# Sheet1.net
KiCad netlist of a schematic drawn in Altium Designer
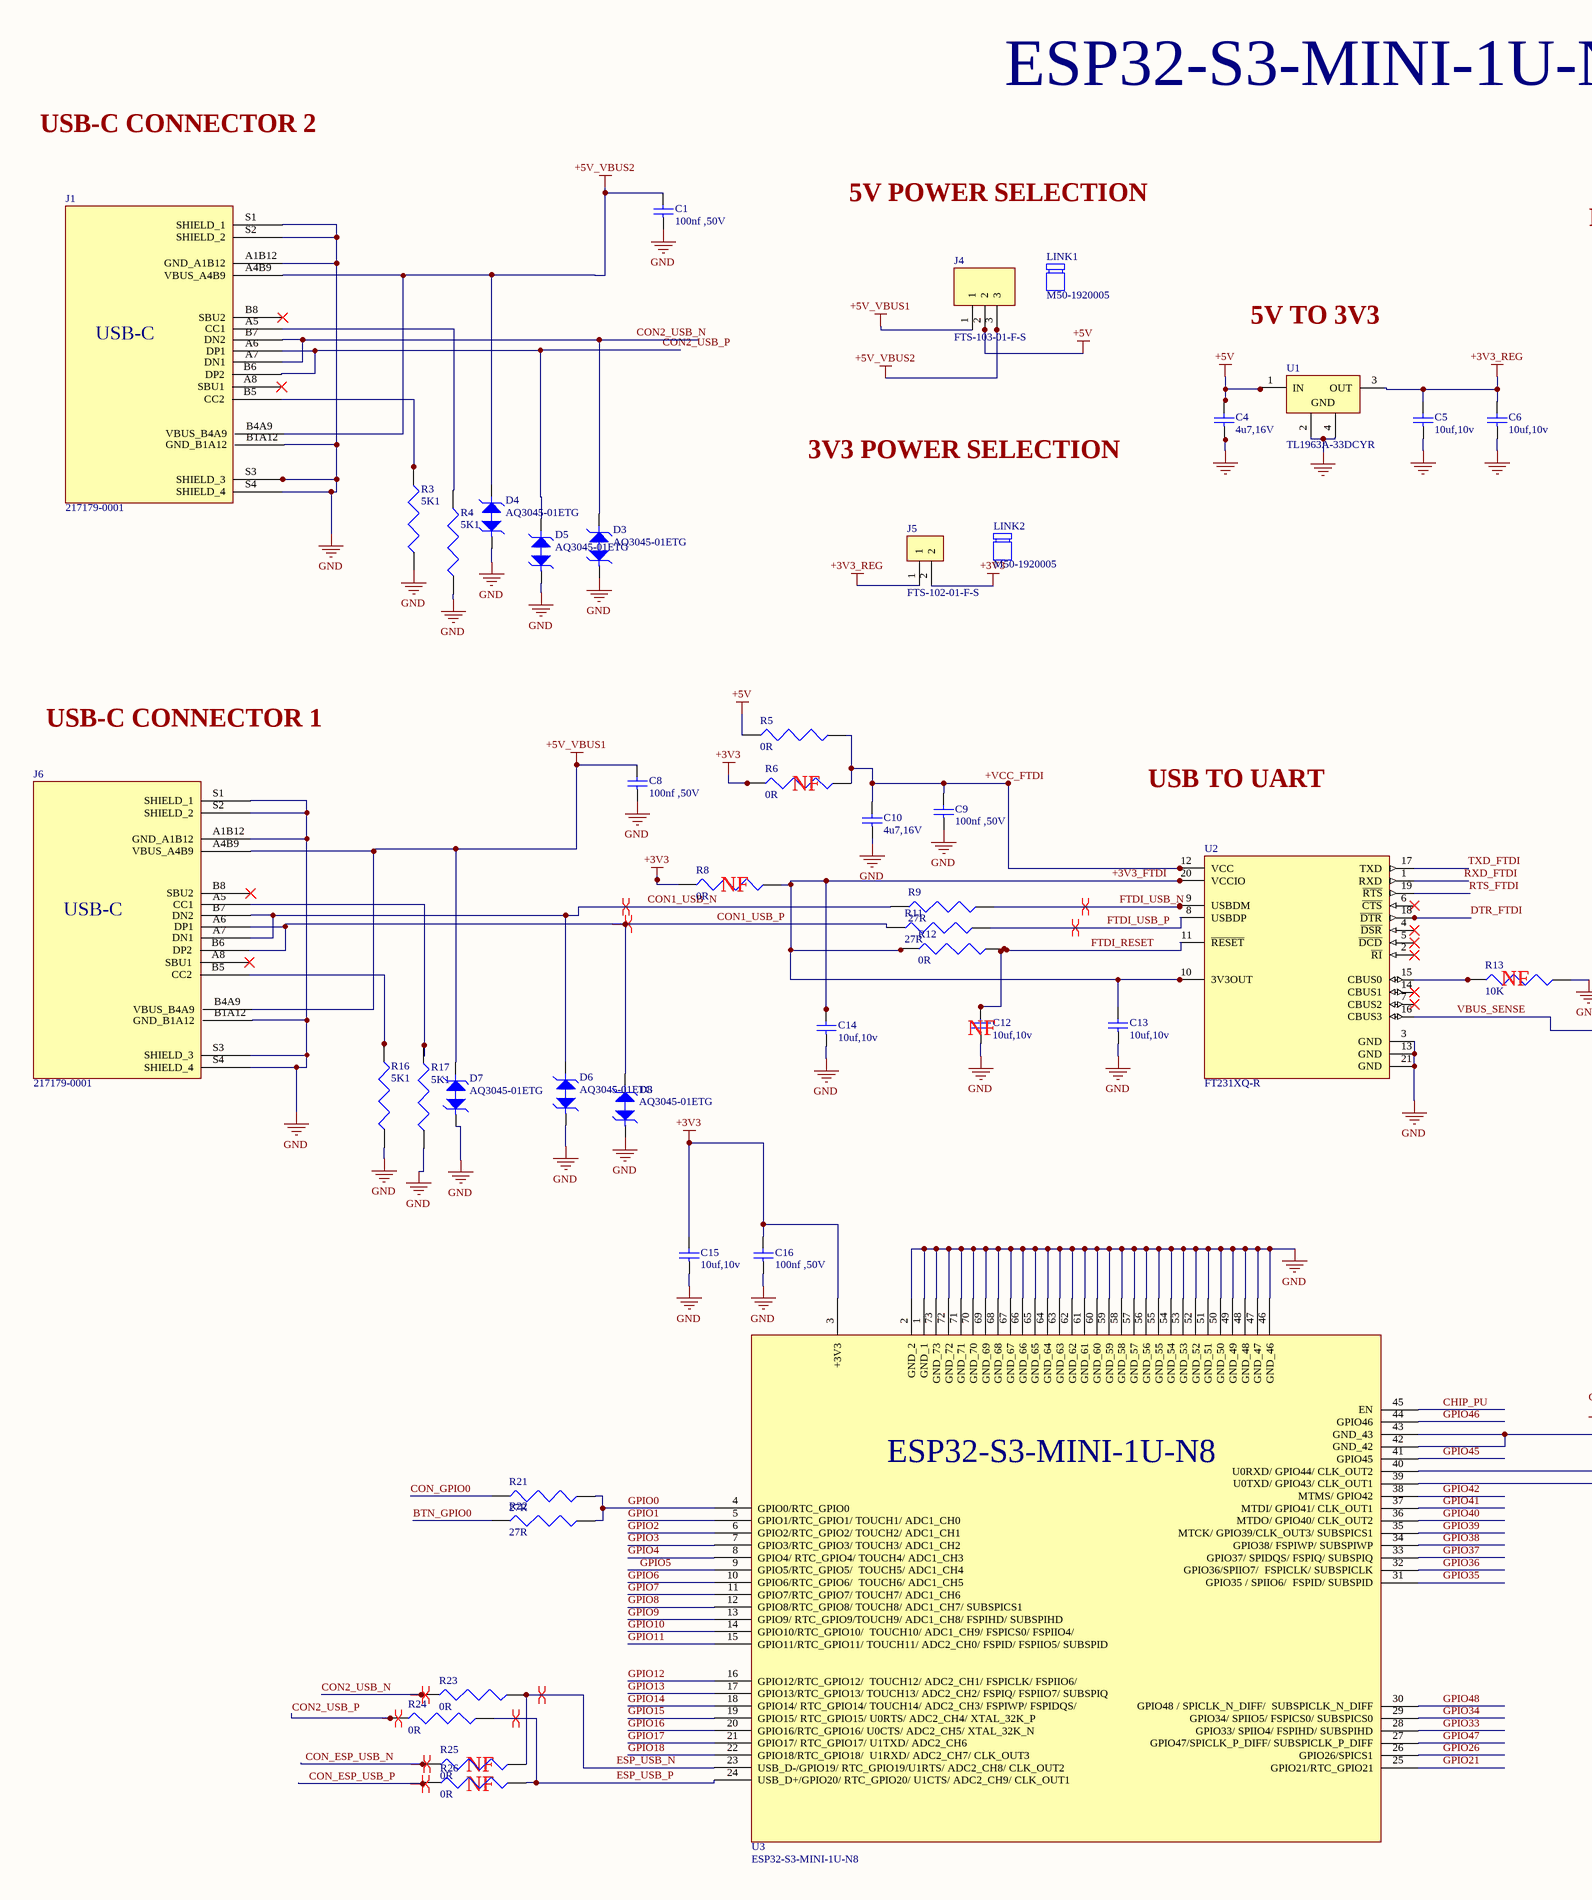
[diagram p0: Sheet1.SchDoc, left]
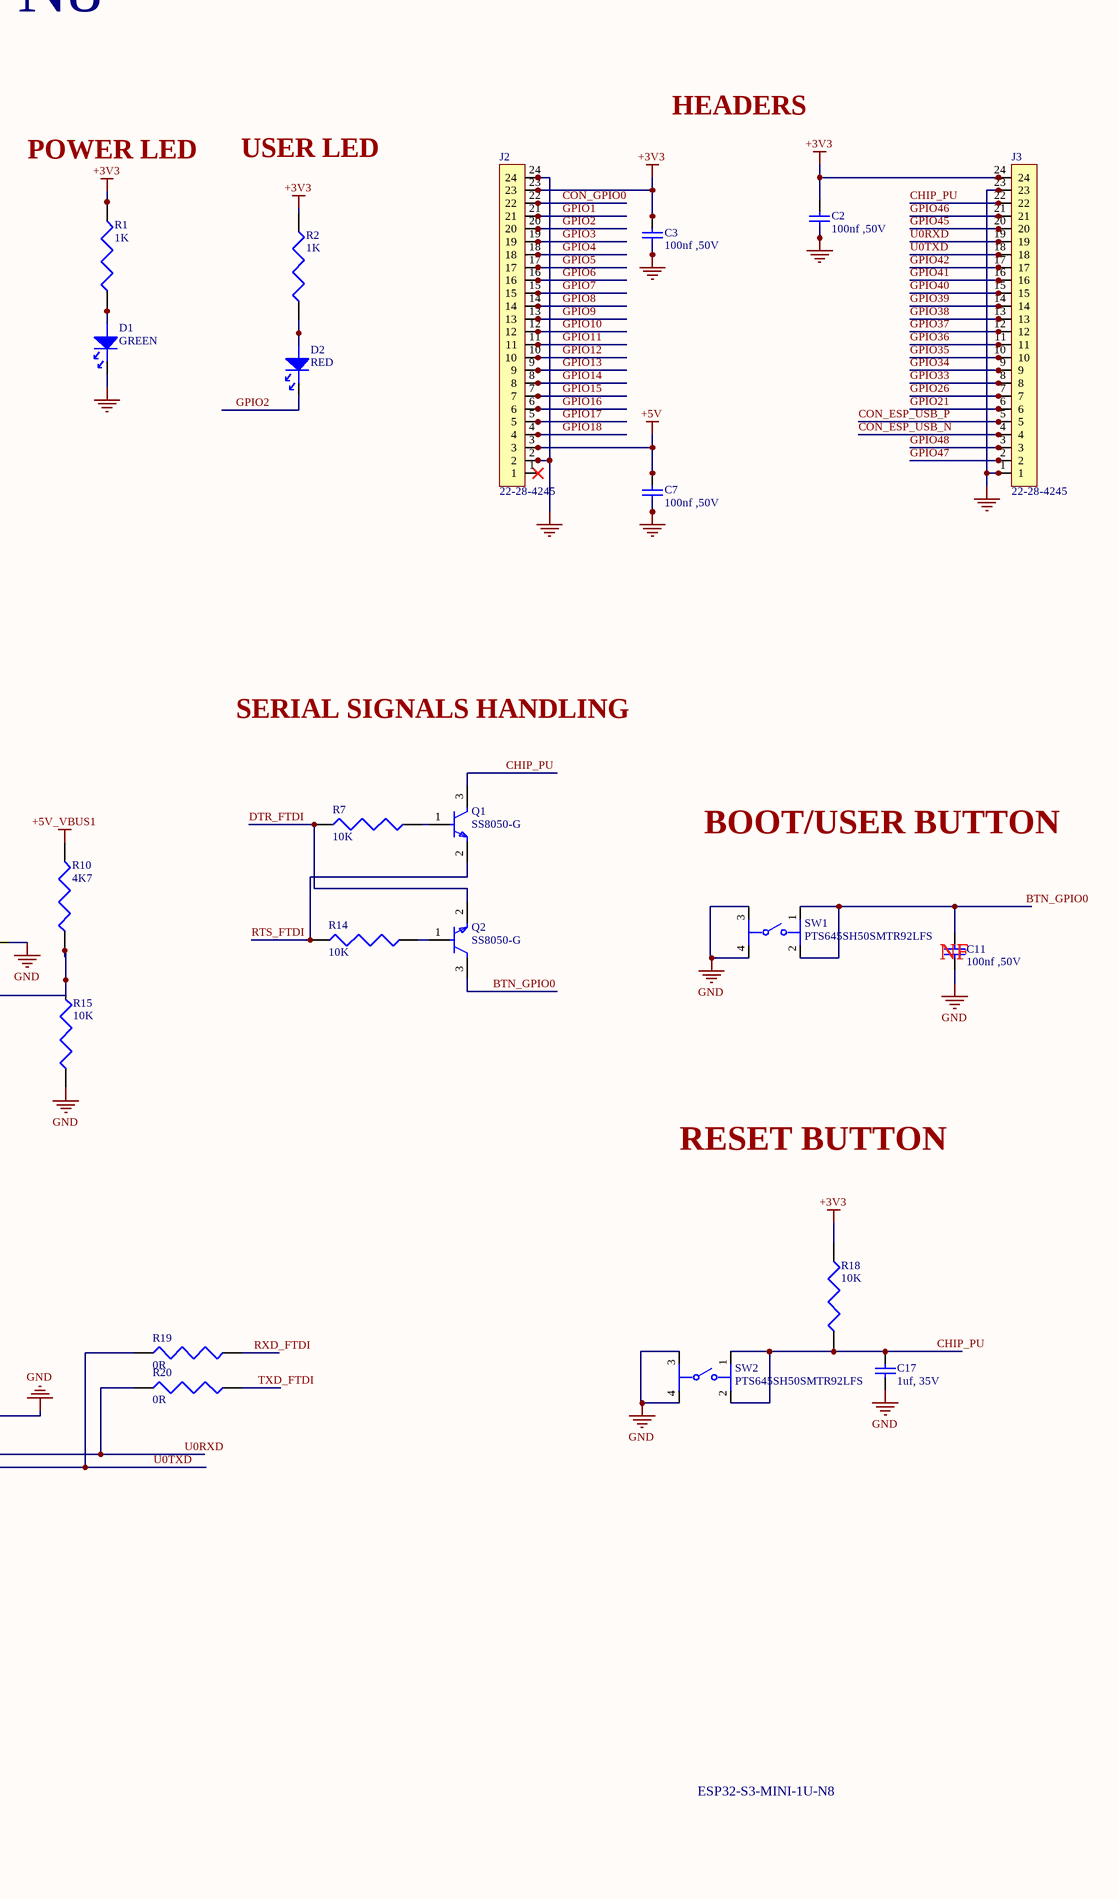
[diagram p1: Sheet1.SchDoc, right]

(export (version "E")
  (design (tool "Eeschema 10.0.6"))
  (components
    (comp (ref "C1")
      (value "100nf ,50V")
      (footprint "CAPC1005X70N")
      (description "CAP CER 0.1UF 10V X7R 0402")
      (fields
        (field (name "MANUFACTURER") "Samsung")
        (field (name "MANUFACTURER PART NUMBER") "CL05B104KP5NNNC")
      )
      (libsource (lib "Schlib1") (part "CL05B104KP5NNNC"))
    )
    (comp (ref "C2")
      (value "100nf ,50V")
      (footprint "CAPC1005X70N")
      (description "CAP CER 0.1UF 10V X7R 0402")
      (fields
        (field (name "MANUFACTURER") "Samsung")
        (field (name "MANUFACTURER PART NUMBER") "CL05B104KP5NNNC")
      )
      (libsource (lib "Schlib1") (part "CL05B104KP5NNNC"))
    )
    (comp (ref "C3")
      (value "100nf ,50V")
      (footprint "CAPC1005X70N")
      (description "CAP CER 0.1UF 10V X7R 0402")
      (fields
        (field (name "MANUFACTURER") "Samsung")
        (field (name "MANUFACTURER PART NUMBER") "CL05B104KP5NNNC")
      )
      (libsource (lib "Schlib1") (part "CL05B104KP5NNNC"))
    )
    (comp (ref "C4")
      (value "4u7,16V")
      (footprint "CAPC1005X70N")
      (description "CAP CER 4.7UF 16V X5R 0402")
      (fields
        (field (name "MANUFACTURER") "Samsung")
        (field (name "MANUFACTURER PART NUMBER") "CL05A475MO5NUNC")
      )
      (libsource (lib "Schlib1") (part "CL05A475MO5NUNC"))
    )
    (comp (ref "C5")
      (value "10uf,10v")
      (footprint "CAPC1005X70N")
      (description "CAP CER 10UF 10V X5R 0402")
      (fields
        (field (name "MANUFACTURER") "Samsung")
        (field (name "MANUFACTURER PART NUMBER") "CL05A106MP8NUB8")
      )
      (libsource (lib "Schlib1") (part "CL05A106MP8NUB8"))
    )
    (comp (ref "C6")
      (value "10uf,10v")
      (footprint "CAPC1005X70N")
      (description "CAP CER 10UF 10V X5R 0402")
      (fields
        (field (name "MANUFACTURER") "Samsung")
        (field (name "MANUFACTURER PART NUMBER") "CL05A106MP8NUB8")
      )
      (libsource (lib "Schlib1") (part "CL05A106MP8NUB8"))
    )
    (comp (ref "C7")
      (value "100nf ,50V")
      (footprint "CAPC1005X70N")
      (description "CAP CER 0.1UF 10V X7R 0402")
      (fields
        (field (name "MANUFACTURER") "Samsung")
        (field (name "MANUFACTURER PART NUMBER") "CL05B104KP5NNNC")
      )
      (libsource (lib "Schlib1") (part "CL05B104KP5NNNC"))
    )
    (comp (ref "C8")
      (value "100nf ,50V")
      (footprint "CAPC1005X70N")
      (description "CAP CER 0.1UF 10V X7R 0402")
      (fields
        (field (name "MANUFACTURER") "Samsung")
        (field (name "MANUFACTURER PART NUMBER") "CL05B104KP5NNNC")
      )
      (libsource (lib "Schlib1") (part "CL05B104KP5NNNC"))
    )
    (comp (ref "C9")
      (value "100nf ,50V")
      (footprint "CAPC1005X70N")
      (description "CAP CER 0.1UF 10V X7R 0402")
      (fields
        (field (name "MANUFACTURER") "Samsung")
        (field (name "MANUFACTURER PART NUMBER") "CL05B104KP5NNNC")
      )
      (libsource (lib "Schlib1") (part "CL05B104KP5NNNC"))
    )
    (comp (ref "C10")
      (value "4u7,16V")
      (footprint "CAPC1005X70N")
      (description "CAP CER 4.7UF 16V X5R 0402")
      (fields
        (field (name "MANUFACTURER") "Samsung")
        (field (name "MANUFACTURER PART NUMBER") "CL05A475MO5NUNC")
      )
      (libsource (lib "Schlib1") (part "CL05A475MO5NUNC"))
    )
    (comp (ref "C11")
      (value "100nf ,50V")
      (footprint "CAPC1005X70N")
      (description "CAP CER 0.1UF 10V X7R 0402")
      (fields
        (field (name "MANUFACTURER") "Samsung")
        (field (name "MANUFACTURER PART NUMBER") "CL05B104KP5NNNC")
      )
      (libsource (lib "Schlib1") (part "CL05B104KP5NNNC"))
    )
    (comp (ref "C12")
      (value "10uf,10v")
      (footprint "CAPC1005X70N")
      (description "CAP CER 10UF 10V X5R 0402")
      (fields
        (field (name "MANUFACTURER") "Samsung")
        (field (name "MANUFACTURER PART NUMBER") "CL05A106MP8NUB8")
      )
      (libsource (lib "Schlib1") (part "CL05A106MP8NUB8"))
    )
    (comp (ref "C13")
      (value "10uf,10v")
      (footprint "CAPC1005X70N")
      (description "CAP CER 10UF 10V X5R 0402")
      (fields
        (field (name "MANUFACTURER") "Samsung")
        (field (name "MANUFACTURER PART NUMBER") "CL05A106MP8NUB8")
      )
      (libsource (lib "Schlib1") (part "CL05A106MP8NUB8"))
    )
    (comp (ref "C14")
      (value "10uf,10v")
      (footprint "CAPC1005X70N")
      (description "CAP CER 10UF 10V X5R 0402")
      (fields
        (field (name "MANUFACTURER") "Samsung")
        (field (name "MANUFACTURER PART NUMBER") "CL05A106MP8NUB8")
      )
      (libsource (lib "Schlib1") (part "CL05A106MP8NUB8"))
    )
    (comp (ref "C15")
      (value "10uf,10v")
      (footprint "CAPC1005X70N")
      (description "CAP CER 10UF 10V X5R 0402")
      (fields
        (field (name "MANUFACTURER") "Samsung")
        (field (name "MANUFACTURER PART NUMBER") "CL05A106MP8NUB8")
      )
      (libsource (lib "Schlib1") (part "CL05A106MP8NUB8"))
    )
    (comp (ref "C16")
      (value "100nf ,50V")
      (footprint "CAPC1005X70N")
      (description "CAP CER 0.1UF 10V X7R 0402")
      (fields
        (field (name "MANUFACTURER") "Samsung")
        (field (name "MANUFACTURER PART NUMBER") "CL05B104KP5NNNC")
      )
      (libsource (lib "Schlib1") (part "CL05B104KP5NNNC"))
    )
    (comp (ref "C17")
      (value "1uf, 35V")
      (footprint "CAPC1005X70N")
      (description "CAP CER 1UF 35V X5R 0402")
      (fields
        (field (name "MANUFACTURER") "Samsung")
        (field (name "MANUFACTURER PART NUMBER") "CL05A105KL5NRNC")
      )
      (libsource (lib "Schlib1") (part "CL05A105KL5NRNC"))
    )
    (comp (ref "D1")
      (value "GREEN")
      (footprint "LED0402G")
      (description "LED YLW-GRN 0402 SMD")
      (fields
        (field (name "MANUFACTURER") "Vishay")
        (field (name "MANUFACTURER PART NUMBER") "VLMG1500-GS08")
      )
      (libsource (lib "Schlib1") (part "VLMG1500-GS08"))
    )
    (comp (ref "D2")
      (value "RED")
      (footprint "LED0402G")
      (description "LED RED 0402 SMD")
      (fields
        (field (name "MANUFACTURER") "Vishay")
        (field (name "MANUFACTURER PART NUMBER") "VLMS1500-GS08")
      )
      (libsource (lib "Schlib1") (part "VLMS1500-GS08"))
    )
    (comp (ref "D3")
      (value "AQ3045-01ETG")
      (footprint "SOD882")
      (description "TVS DIODE 5.3VWM 12VC SOD882")
      (fields (field (name "MANUFACTURER") "Littelfuse"))
      (libsource (lib "Schlib1") (part "AQ3045-01ETG"))
    )
    (comp (ref "D4")
      (value "AQ3045-01ETG")
      (footprint "SOD882")
      (description "TVS DIODE 5.3VWM 12VC SOD882")
      (fields (field (name "MANUFACTURER") "Littelfuse"))
      (libsource (lib "Schlib1") (part "AQ3045-01ETG"))
    )
    (comp (ref "D5")
      (value "AQ3045-01ETG")
      (footprint "SOD882")
      (description "TVS DIODE 5.3VWM 12VC SOD882")
      (fields (field (name "MANUFACTURER") "Littelfuse"))
      (libsource (lib "Schlib1") (part "AQ3045-01ETG"))
    )
    (comp (ref "D6")
      (value "AQ3045-01ETG")
      (footprint "SOD882")
      (description "TVS DIODE 5.3VWM 12VC SOD882")
      (fields (field (name "MANUFACTURER") "Littelfuse"))
      (libsource (lib "Schlib1") (part "AQ3045-01ETG"))
    )
    (comp (ref "D7")
      (value "AQ3045-01ETG")
      (footprint "SOD882")
      (description "TVS DIODE 5.3VWM 12VC SOD882")
      (fields (field (name "MANUFACTURER") "Littelfuse"))
      (libsource (lib "Schlib1") (part "AQ3045-01ETG"))
    )
    (comp (ref "D8")
      (value "AQ3045-01ETG")
      (footprint "SOD882")
      (description "TVS DIODE 5.3VWM 12VC SOD882")
      (fields (field (name "MANUFACTURER") "Littelfuse"))
      (libsource (lib "Schlib1") (part "AQ3045-01ETG"))
    )
    (comp (ref "J1")
      (value "217179-0001")
      (footprint "FP-2171790001-MFG")
      (description "CONN RCP USB2.0 TYP C 24P SMD RA")
      (fields (field (name "MANUFACTURER") "Molex"))
      (libsource (lib "Schlib1") (part "217179-0001"))
    )
    (comp (ref "J2")
      (value "22-28-4245")
      (footprint "HDR_1X24_2.54mm")
      (description "CONN HEADER VERT 24POS 2.54MM")
      (fields (field (name "MANUFACTURER") "Molex") (field (name "LCSC PART NUMBER") "C7145888"))
      (libsource (lib "") (part "22-28-4245_1"))
    )
    (comp (ref "J3")
      (value "22-28-4245")
      (footprint "HDR_1X24_2.54mm")
      (description "CONN HEADER VERT 24POS 2.54MM")
      (fields (field (name "MANUFACTURER") "Molex") (field (name "LCSC PART NUMBER") "C7145888"))
      (libsource (lib "Schlib1") (part "22-28-4245"))
    )
    (comp (ref "J4")
      (value "FTS-103-01-F-S")
      (footprint "HDR_1X3_2.54mm - duplicate")
      (description "CONN HEADER VERT 3POS 1.27MM")
      (fields (field (name "MANUFACTURER") "Samtec") (field (name "LCSC PART NUMBER") "C3333578"))
      (libsource (lib "Schlib1") (part "FTS-103-01-F-S"))
    )
    (comp (ref "J5")
      (value "FTS-102-01-F-S")
      (footprint "HDR_1X2_2.54mm")
      (description "CONN HEADER VERT 2POS 1.27MM")
      (fields (field (name "MANUFACTURER") "Samtec") (field (name "LCSC PART NUMBER") "C6045317"))
      (libsource (lib "Schlib1") (part "FTS-102-01-F-S"))
    )
    (comp (ref "J6")
      (value "217179-0001")
      (footprint "FP-2171790001-MFG")
      (description "CONN RCP USB2.0 TYP C 24P SMD RA")
      (fields (field (name "MANUFACTURER") "Molex"))
      (libsource (lib "Schlib1") (part "217179-0001"))
    )
    (comp (ref "LINK1")
      (value "M50-1920005")
      (description "CONN SHUNT 1.27MM RED")
      (fields (field (name "MANUFACTURER") "Harwin") (field (name "LCSC PART NUMBER") "C6985646"))
      (libsource (lib "Schlib1") (part "M50-1920005"))
    )
    (comp (ref "LINK2")
      (value "M50-1920005")
      (description "CONN SHUNT 1.27MM RED")
      (fields (field (name "MANUFACTURER") "Harwin") (field (name "LCSC PART NUMBER") "C6985646"))
      (libsource (lib "Schlib1") (part "M50-1920005"))
    )
    (comp (ref "Q1")
      (value "SS8050-G")
      (footprint "FP-SS8050-G-IPC_B")
      (description "TRANS NPN 25V 1.5A SOT23-3")
      (fields (field (name "MANUFACTURER") "Comchip") (field (name "PARAMETER 1LCSC PART NUMBER") "C164886"))
      (libsource (lib "Schlib1") (part "SS8050-G"))
    )
    (comp (ref "Q2")
      (value "SS8050-G")
      (footprint "FP-SS8050-G-IPC_B")
      (description "TRANS NPN 25V 1.5A SOT23-3")
      (fields (field (name "MANUFACTURER") "Comchip") (field (name "PARAMETER 1LCSC PART NUMBER") "C164886"))
      (libsource (lib "Schlib1") (part "SS8050-G"))
    )
    (comp (ref "R1")
      (value "1K")
      (footprint "RESC1005X37N")
      (description "RES 1K OHM 1% 1/16W 0402")
      (fields
        (field (name "MANUFACTURER") "Yageo")
        (field (name "MANUFACTURER PART NUMBER") "RC0402FR-071KL")
      )
      (libsource (lib "Schlib1") (part "RC0402FR-071KL"))
    )
    (comp (ref "R2")
      (value "1K")
      (footprint "RESC1005X37N")
      (description "RES 1K OHM 1% 1/16W 0402")
      (fields
        (field (name "MANUFACTURER") "Yageo")
        (field (name "MANUFACTURER PART NUMBER") "RC0402FR-071KL")
      )
      (libsource (lib "Schlib1") (part "RC0402FR-071KL"))
    )
    (comp (ref "R3")
      (value "5K1")
      (footprint "RESC1005X37N")
      (description "RES SMD 5.1K OHM 1% 1/16W 0402")
      (fields
        (field (name "MANUFACTURER") "Yageo")
        (field (name "MANUFACTURER PART NUMBER") "AC0402FR-075K1L")
      )
      (libsource (lib "Schlib1") (part "AC0402FR-075K1L"))
    )
    (comp (ref "R4")
      (value "5K1")
      (footprint "RESC1005X37N")
      (description "RES SMD 5.1K OHM 1% 1/16W 0402")
      (fields
        (field (name "MANUFACTURER") "Yageo")
        (field (name "MANUFACTURER PART NUMBER") "AC0402FR-075K1L")
      )
      (libsource (lib "Schlib1") (part "AC0402FR-075K1L"))
    )
    (comp (ref "R5")
      (value "0R")
      (footprint "RESC1005X37N")
      (description "RES 0 OHM JUMPER 1/16W 0402")
      (fields
        (field (name "MANUFACTURER") "Yageo")
        (field (name "MANUFACTURER PART NUMBER") "RC0402JR-070RL")
      )
      (libsource (lib "Schlib1") (part "RC0402JR-070RL (2)"))
    )
    (comp (ref "R6")
      (value "0R")
      (footprint "RESC1005X37N")
      (description "RES 0 OHM JUMPER 1/16W 0402")
      (fields
        (field (name "MANUFACTURER") "Yageo")
        (field (name "MANUFACTURER PART NUMBER") "RC0402JR-070RL")
      )
      (libsource (lib "Schlib1") (part "RC0402JR-070RL (2)"))
    )
    (comp (ref "R7")
      (value "10K")
      (footprint "RESC1005X37N")
      (description "RES SMD 10K OHM 1% 1/16W 0402")
      (fields
        (field (name "MANUFACTURER") "Yageo")
        (field (name "MANUFACTURER PART NUMBER") "AC0402FR-0710KL")
      )
      (libsource (lib "Schlib1") (part "AC0402FR-0710KL"))
    )
    (comp (ref "R8")
      (value "0R")
      (footprint "RESC1005X37N")
      (description "RES 0 OHM JUMPER 1/16W 0402")
      (fields
        (field (name "MANUFACTURER") "Yageo")
        (field (name "MANUFACTURER PART NUMBER") "RC0402JR-070RL")
      )
      (libsource (lib "Schlib1") (part "RC0402JR-070RL (2)"))
    )
    (comp (ref "R9")
      (value "27R")
      (footprint "RESC1005X37N")
      (description "RES 27R OHM JUMPER 1/16W 0402")
      (fields
        (field (name "MANUFACTURER") "Yageo")
        (field (name "MANUFACTURER PART NUMBER") "RC0402FR-0727RL")
      )
      (libsource (lib "Schlib1") (part "RC0402FR-0727RL"))
    )
    (comp (ref "R10")
      (value "4K7")
      (footprint "RESC1005X37N")
      (description "RES 4.7K OHM 1% 1/16W 0402")
      (fields
        (field (name "MANUFACTURER") "Yageo")
        (field (name "MANUFACTURER PART NUMBER") "RC0402FR-074K7L")
      )
      (libsource (lib "Schlib1") (part "RC0402FR-074K7L"))
    )
    (comp (ref "R11")
      (value "27R")
      (footprint "RESC1005X37N")
      (description "RES 27R OHM JUMPER 1/16W 0402")
      (fields
        (field (name "MANUFACTURER") "Yageo")
        (field (name "MANUFACTURER PART NUMBER") "RC0402FR-0727RL")
      )
      (libsource (lib "Schlib1") (part "RC0402FR-0727RL"))
    )
    (comp (ref "R12")
      (value "0R")
      (footprint "RESC1005X37N")
      (description "RES 0 OHM JUMPER 1/16W 0402")
      (fields
        (field (name "MANUFACTURER") "Yageo")
        (field (name "MANUFACTURER PART NUMBER") "RC0402JR-070RL")
      )
      (libsource (lib "Schlib1") (part "RC0402JR-070RL (2)"))
    )
    (comp (ref "R13")
      (value "10K")
      (footprint "RESC1005X37N")
      (description "RES SMD 10K OHM 1% 1/16W 0402")
      (fields
        (field (name "MANUFACTURER") "Yageo")
        (field (name "MANUFACTURER PART NUMBER") "AC0402FR-0710KL")
      )
      (libsource (lib "Schlib1") (part "AC0402FR-0710KL"))
    )
    (comp (ref "R14")
      (value "10K")
      (footprint "RESC1005X37N")
      (description "RES SMD 10K OHM 1% 1/16W 0402")
      (fields
        (field (name "MANUFACTURER") "Yageo")
        (field (name "MANUFACTURER PART NUMBER") "AC0402FR-0710KL")
      )
      (libsource (lib "Schlib1") (part "AC0402FR-0710KL"))
    )
    (comp (ref "R15")
      (value "10K")
      (footprint "RESC1005X37N")
      (description "RES SMD 10K OHM 1% 1/16W 0402")
      (fields
        (field (name "MANUFACTURER") "Yageo")
        (field (name "MANUFACTURER PART NUMBER") "AC0402FR-0710KL")
      )
      (libsource (lib "Schlib1") (part "AC0402FR-0710KL"))
    )
    (comp (ref "R16")
      (value "5K1")
      (footprint "RESC1005X37N")
      (description "RES SMD 5.1K OHM 1% 1/16W 0402")
      (fields
        (field (name "MANUFACTURER") "Yageo")
        (field (name "MANUFACTURER PART NUMBER") "AC0402FR-075K1L")
      )
      (libsource (lib "Schlib1") (part "AC0402FR-075K1L"))
    )
    (comp (ref "R17")
      (value "5K1")
      (footprint "RESC1005X37N")
      (description "RES SMD 5.1K OHM 1% 1/16W 0402")
      (fields
        (field (name "MANUFACTURER") "Yageo")
        (field (name "MANUFACTURER PART NUMBER") "AC0402FR-075K1L")
      )
      (libsource (lib "Schlib1") (part "AC0402FR-075K1L"))
    )
    (comp (ref "R18")
      (value "10K")
      (footprint "RESC1005X37N")
      (description "RES SMD 10K OHM 1% 1/16W 0402")
      (fields
        (field (name "MANUFACTURER") "Yageo")
        (field (name "MANUFACTURER PART NUMBER") "AC0402FR-0710KL")
      )
      (libsource (lib "Schlib1") (part "AC0402FR-0710KL"))
    )
    (comp (ref "R19")
      (value "0R")
      (footprint "RESC1005X37N")
      (description "RES 0 OHM JUMPER 1/16W 0402")
      (fields
        (field (name "MANUFACTURER") "Yageo")
        (field (name "MANUFACTURER PART NUMBER") "RC0402JR-070RL")
      )
      (libsource (lib "Schlib1") (part "RC0402JR-070RL (2)"))
    )
    (comp (ref "R20")
      (value "0R")
      (footprint "RESC1005X37N")
      (description "RES 0 OHM JUMPER 1/16W 0402")
      (fields
        (field (name "MANUFACTURER") "Yageo")
        (field (name "MANUFACTURER PART NUMBER") "RC0402JR-070RL")
      )
      (libsource (lib "Schlib1") (part "RC0402JR-070RL (2)"))
    )
    (comp (ref "R21")
      (value "27R")
      (footprint "RESC1005X37N")
      (description "RES 27R OHM JUMPER 1/16W 0402")
      (fields
        (field (name "MANUFACTURER") "Yageo")
        (field (name "MANUFACTURER PART NUMBER") "RC0402FR-0727RL")
      )
      (libsource (lib "Schlib1") (part "RC0402FR-0727RL"))
    )
    (comp (ref "R22")
      (value "27R")
      (footprint "RESC1005X37N")
      (description "RES 27R OHM JUMPER 1/16W 0402")
      (fields
        (field (name "MANUFACTURER") "Yageo")
        (field (name "MANUFACTURER PART NUMBER") "RC0402FR-0727RL")
      )
      (libsource (lib "Schlib1") (part "RC0402FR-0727RL"))
    )
    (comp (ref "R23")
      (value "0R")
      (footprint "RESC1005X37N")
      (description "RES 0 OHM JUMPER 1/16W 0402")
      (fields
        (field (name "MANUFACTURER") "Yageo")
        (field (name "MANUFACTURER PART NUMBER") "RC0402JR-070RL")
      )
      (libsource (lib "Schlib1") (part "RC0402JR-070RL (2)"))
    )
    (comp (ref "R24")
      (value "0R")
      (footprint "RESC1005X37N")
      (description "RES 0 OHM JUMPER 1/16W 0402")
      (fields
        (field (name "MANUFACTURER") "Yageo")
        (field (name "MANUFACTURER PART NUMBER") "RC0402JR-070RL")
      )
      (libsource (lib "Schlib1") (part "RC0402JR-070RL (2)"))
    )
    (comp (ref "R25")
      (value "0R")
      (footprint "RESC1005X37N")
      (description "RES 0 OHM JUMPER 1/16W 0402")
      (fields
        (field (name "MANUFACTURER") "Yageo")
        (field (name "MANUFACTURER PART NUMBER") "RC0402JR-070RL")
      )
      (libsource (lib "Schlib1") (part "RC0402JR-070RL (2)"))
    )
    (comp (ref "R26")
      (value "0R")
      (footprint "RESC1005X37N")
      (description "RES 0 OHM JUMPER 1/16W 0402")
      (fields
        (field (name "MANUFACTURER") "Yageo")
        (field (name "MANUFACTURER PART NUMBER") "RC0402JR-070RL")
      )
      (libsource (lib "Schlib1") (part "RC0402JR-070RL (2)"))
    )
    (comp (ref "SW1")
      (value "PTS645SH50SMTR92LFS")
      (footprint "FP-PTS645SH50SMTR92LFS-MFG")
      (description "SWITCH TACTILE SPST-NO 0.05A 12V")
      (fields (field (name "MANUFACTURER") "ITT C&K") (field (name "LCSC PART") "C221869"))
      (libsource (lib "Schlib1") (part "PTS645SH50SMTR92LFS"))
    )
    (comp (ref "SW2")
      (value "PTS645SH50SMTR92LFS")
      (footprint "FP-PTS645SH50SMTR92LFS-MFG")
      (description "SWITCH TACTILE SPST-NO 0.05A 12V")
      (fields (field (name "MANUFACTURER") "ITT C&K") (field (name "LCSC PART") "C221869"))
      (libsource (lib "Schlib1") (part "PTS645SH50SMTR92LFS"))
    )
    (comp (ref "U1")
      (value "TL1963A-33DCYR")
      (footprint "TL1963A-33DCYR")
      (description "IC REG LINEAR 3.3V 1.5A SOT223-4")
      (fields (field (name "MANUFACTURER") "Texas Instruments") (field (name "LCSC PART NUMBER") "C181262"))
      (libsource (lib "Schlib1") (part "TL1963A-33DCYR"))
    )
    (comp (ref "U2")
      (value "FT231XQ-R")
      (footprint "FP-QFN-20-IPC_B")
      (description "Microprocessor Circuit, CMOS")
      (fields (field (name "MANUFACTURER") "FTDI") (field (name "LCSC PART NUMBER") "C132159"))
      (libsource (lib "Schlib1") (part "FT231XQ-R"))
    )
    (comp (ref "U3")
      (value "ESP32-S3-MINI-1U-N8")
      (footprint "XCVR_ESP32-S3-MINI-1-N8")
      (fields (field (name "MANUFACTURER") "Espressif Systems") (field (name "LCSC PART") "C2980299"))
      (libsource (lib "Schlib1") (part "ESP32-S3-MINI-1U-N8"))
    )
  )
  (nets
    (net (code "1") (name "+3V3") (class "Default")
      (node (ref "C15") (pin "2") (pinfunction "2_2") (pintype "passive"))
      (node (ref "C16") (pin "2") (pinfunction "2_2") (pintype "passive"))
      (node (ref "C2") (pin "2") (pinfunction "2_2") (pintype "passive"))
      (node (ref "C3") (pin "2") (pinfunction "2_2") (pintype "passive"))
      (node (ref "J2") (pin "23") (pinfunction "23_23") (pintype "passive"))
      (node (ref "J3") (pin "24") (pinfunction "24_24") (pintype "passive"))
      (node (ref "J5") (pin "2") (pinfunction "2_2") (pintype "passive"))
      (node (ref "R1") (pin "2") (pinfunction "2_2") (pintype "passive"))
      (node (ref "R18") (pin "2") (pinfunction "2_2") (pintype "passive"))
      (node (ref "R2") (pin "2") (pinfunction "2_2") (pintype "passive"))
      (node (ref "R6") (pin "1") (pinfunction "1_1") (pintype "passive"))
      (node (ref "R8") (pin "1") (pinfunction "1_1") (pintype "passive"))
      (node (ref "U3") (pin "3") (pinfunction "+3V3_3") (pintype "passive"))
    )
    (net (code "2") (name "+3V3_REG") (class "Default")
      (node (ref "C5") (pin "2") (pinfunction "2_2") (pintype "passive"))
      (node (ref "C6") (pin "2") (pinfunction "2_2") (pintype "passive"))
      (node (ref "J5") (pin "1") (pinfunction "1_1") (pintype "passive"))
      (node (ref "U1") (pin "3") (pinfunction "OUT_3") (pintype "power_in"))
    )
    (net (code "3") (name "+5V") (class "Default")
      (node (ref "C4") (pin "2") (pinfunction "2_2") (pintype "passive"))
      (node (ref "C7") (pin "2") (pinfunction "2_2") (pintype "passive"))
      (node (ref "J2") (pin "3") (pinfunction "3_3") (pintype "passive"))
      (node (ref "J4") (pin "2") (pinfunction "2_2") (pintype "passive"))
      (node (ref "R5") (pin "2") (pinfunction "2_2") (pintype "passive"))
      (node (ref "U1") (pin "1") (pinfunction "IN_1") (pintype "power_in"))
    )
    (net (code "4") (name "+5V_VBUS1") (class "Default")
      (node (ref "C8") (pin "2") (pinfunction "2_2") (pintype "passive"))
      (node (ref "D7") (pin "2") (pinfunction "2_2") (pintype "passive"))
      (node (ref "J4") (pin "1") (pinfunction "1_1") (pintype "passive"))
      (node (ref "J6") (pin "A4B9") (pinfunction "VBUS_A4B9_A4B9") (pintype "passive"))
      (node (ref "J6") (pin "B4A9") (pinfunction "VBUS_B4A9_B4A9") (pintype "passive"))
      (node (ref "R10") (pin "2") (pinfunction "2_2") (pintype "passive"))
    )
    (net (code "5") (name "+5V_VBUS2") (class "Default")
      (node (ref "C1") (pin "2") (pinfunction "2_2") (pintype "passive"))
      (node (ref "D4") (pin "2") (pinfunction "2_2") (pintype "passive"))
      (node (ref "J1") (pin "A4B9") (pinfunction "VBUS_A4B9_A4B9") (pintype "passive"))
      (node (ref "J1") (pin "B4A9") (pinfunction "VBUS_B4A9_B4A9") (pintype "passive"))
      (node (ref "J4") (pin "3") (pinfunction "3_3") (pintype "passive"))
    )
    (net (code "6") (name "/+3V3_FTDI") (class "Default")
      (node (ref "C13") (pin "2") (pinfunction "2_2") (pintype "passive"))
      (node (ref "C14") (pin "2") (pinfunction "2_2") (pintype "passive"))
      (node (ref "R12") (pin "1") (pinfunction "1_1") (pintype "passive"))
      (node (ref "R8") (pin "2") (pinfunction "2_2") (pintype "passive"))
      (node (ref "U2") (pin "10") (pinfunction "3V3OUT_10") (pintype "passive"))
      (node (ref "U2") (pin "20") (pinfunction "VCCIO_20") (pintype "power_in"))
    )
    (net (code "7") (name "/+VCC_FTDI") (class "Default")
      (node (ref "C10") (pin "2") (pinfunction "2_2") (pintype "passive"))
      (node (ref "C9") (pin "2") (pinfunction "2_2") (pintype "passive"))
      (node (ref "R5") (pin "1") (pinfunction "1_1") (pintype "passive"))
      (node (ref "R6") (pin "2") (pinfunction "2_2") (pintype "passive"))
      (node (ref "U2") (pin "12") (pinfunction "VCC_12") (pintype "power_in"))
    )
    (net (code "8") (name "/BTN_GPIO0") (class "Default")
      (node (ref "C11") (pin "2") (pinfunction "2_2") (pintype "passive"))
      (node (ref "Q2") (pin "3") (pinfunction "C_3") (pintype "passive"))
      (node (ref "R22") (pin "1") (pinfunction "1_1") (pintype "passive"))
      (node (ref "SW1") (pin "1") (pinfunction "1_1") (pintype "passive"))
      (node (ref "SW1") (pin "2") (pinfunction "2_2") (pintype "passive"))
    )
    (net (code "9") (name "/CHIP_PU") (class "Default")
      (node (ref "C17") (pin "2") (pinfunction "2_2") (pintype "passive"))
      (node (ref "J3") (pin "22") (pinfunction "22_22") (pintype "passive"))
      (node (ref "Q1") (pin "3") (pinfunction "C_3") (pintype "passive"))
      (node (ref "R18") (pin "1") (pinfunction "1_1") (pintype "passive"))
      (node (ref "SW2") (pin "1") (pinfunction "1_1") (pintype "passive"))
      (node (ref "SW2") (pin "2") (pinfunction "2_2") (pintype "passive"))
      (node (ref "U3") (pin "45") (pinfunction "EN_45") (pintype "passive"))
    )
    (net (code "10") (name "/CON1_USB_N") (class "Default")
      (node (ref "D6") (pin "2") (pinfunction "2_2") (pintype "passive"))
      (node (ref "J6") (pin "A7") (pinfunction "DN1_A7") (pintype "passive"))
      (node (ref "J6") (pin "B7") (pinfunction "DN2_B7") (pintype "passive"))
      (node (ref "R9") (pin "1") (pinfunction "1_1") (pintype "passive"))
    )
    (net (code "11") (name "/CON1_USB_P") (class "Default")
      (node (ref "D8") (pin "2") (pinfunction "2_2") (pintype "passive"))
      (node (ref "J6") (pin "A6") (pinfunction "DP1_A6") (pintype "passive"))
      (node (ref "J6") (pin "B6") (pinfunction "DP2_B6") (pintype "passive"))
      (node (ref "R11") (pin "1") (pinfunction "1_1") (pintype "passive"))
    )
    (net (code "12") (name "/CON2_USB_N") (class "Default")
      (node (ref "D3") (pin "2") (pinfunction "2_2") (pintype "passive"))
      (node (ref "J1") (pin "A7") (pinfunction "DN1_A7") (pintype "passive"))
      (node (ref "J1") (pin "B7") (pinfunction "DN2_B7") (pintype "passive"))
      (node (ref "R23") (pin "1") (pinfunction "1_1") (pintype "passive"))
    )
    (net (code "13") (name "/CON2_USB_P") (class "Default")
      (node (ref "D5") (pin "2") (pinfunction "2_2") (pintype "passive"))
      (node (ref "J1") (pin "A6") (pinfunction "DP1_A6") (pintype "passive"))
      (node (ref "J1") (pin "B6") (pinfunction "DP2_B6") (pintype "passive"))
      (node (ref "R24") (pin "1") (pinfunction "1_1") (pintype "passive"))
    )
    (net (code "14") (name "/CON_ESP_USB_N") (class "Default")
      (node (ref "J3") (pin "4") (pinfunction "4_4") (pintype "passive"))
      (node (ref "R25") (pin "1") (pinfunction "1_1") (pintype "passive"))
    )
    (net (code "15") (name "/CON_ESP_USB_P") (class "Default")
      (node (ref "J3") (pin "5") (pinfunction "5_5") (pintype "passive"))
      (node (ref "R26") (pin "1") (pinfunction "1_1") (pintype "passive"))
    )
    (net (code "16") (name "/CON_GPIO0") (class "Default")
      (node (ref "J2") (pin "22") (pinfunction "22_22") (pintype "passive"))
      (node (ref "R21") (pin "1") (pinfunction "1_1") (pintype "passive"))
    )
    (net (code "17") (name "/DTR_FTDI") (class "Default")
      (node (ref "Q2") (pin "2") (pinfunction "E_2") (pintype "passive"))
      (node (ref "R7") (pin "1") (pinfunction "1_1") (pintype "passive"))
      (node (ref "U2") (pin "18") (pinfunction "~{DTR}_18") (pintype "output"))
    )
    (net (code "18") (name "/ESP_USB_N") (class "Default")
      (node (ref "R23") (pin "2") (pinfunction "2_2") (pintype "passive"))
      (node (ref "R25") (pin "2") (pinfunction "2_2") (pintype "passive"))
      (node (ref "U3") (pin "23") (pinfunction "USB_D-/GPIO19/_RTC_GPIO19/U1RTS/_ADC2_CH8/_CLK_OUT2_23") (pintype "passive"))
    )
    (net (code "19") (name "/ESP_USB_P") (class "Default")
      (node (ref "R24") (pin "2") (pinfunction "2_2") (pintype "passive"))
      (node (ref "R26") (pin "2") (pinfunction "2_2") (pintype "passive"))
      (node (ref "U3") (pin "24") (pinfunction "USB_D+/GPIO20/_RTC_GPIO20/_U1CTS/_ADC2_CH9/_CLK_OUT1_24") (pintype "passive"))
    )
    (net (code "20") (name "/FTDI_RESET") (class "Default")
      (node (ref "C12") (pin "2") (pinfunction "2_2") (pintype "passive"))
      (node (ref "R12") (pin "2") (pinfunction "2_2") (pintype "passive"))
      (node (ref "U2") (pin "11") (pinfunction "~{RESET}_11") (pintype "passive"))
    )
    (net (code "21") (name "/FTDI_USB_N") (class "Default")
      (node (ref "R9") (pin "2") (pinfunction "2_2") (pintype "passive"))
      (node (ref "U2") (pin "9") (pinfunction "USBDM_9") (pintype "passive"))
    )
    (net (code "22") (name "/FTDI_USB_P") (class "Default")
      (node (ref "R11") (pin "2") (pinfunction "2_2") (pintype "passive"))
      (node (ref "U2") (pin "8") (pinfunction "USBDP_8") (pintype "passive"))
    )
    (net (code "23") (name "/GPIO0") (class "Default")
      (node (ref "R21") (pin "2") (pinfunction "2_2") (pintype "passive"))
      (node (ref "R22") (pin "2") (pinfunction "2_2") (pintype "passive"))
      (node (ref "U3") (pin "4") (pinfunction "GPIO0/RTC_GPIO0_4") (pintype "passive"))
    )
    (net (code "24") (name "/GPIO1") (class "Default")
      (node (ref "J2") (pin "21") (pinfunction "21_21") (pintype "passive"))
      (node (ref "U3") (pin "5") (pinfunction "GPIO1/RTC_GPIO1/_TOUCH1/_ADC1_CH0_5") (pintype "passive"))
    )
    (net (code "25") (name "/GPIO2") (class "Default")
      (node (ref "D2") (pin "1") (pinfunction "1_1") (pintype "passive"))
      (node (ref "J2") (pin "20") (pinfunction "20_20") (pintype "passive"))
      (node (ref "U3") (pin "6") (pinfunction "GPIO2/RTC_GPIO2/_TOUCH2/_ADC1_CH1_6") (pintype "passive"))
    )
    (net (code "26") (name "/GPIO3") (class "Default")
      (node (ref "J2") (pin "19") (pinfunction "19_19") (pintype "passive"))
      (node (ref "U3") (pin "7") (pinfunction "GPIO3/RTC_GPIO3/_TOUCH3/_ADC1_CH2_7") (pintype "passive"))
    )
    (net (code "27") (name "/GPIO4") (class "Default")
      (node (ref "J2") (pin "18") (pinfunction "18_18") (pintype "passive"))
      (node (ref "U3") (pin "8") (pinfunction "GPIO4/_RTC_GPIO4/_TOUCH4/_ADC1_CH3_8") (pintype "passive"))
    )
    (net (code "28") (name "/GPIO5") (class "Default")
      (node (ref "J2") (pin "17") (pinfunction "17_17") (pintype "passive"))
      (node (ref "U3") (pin "9") (pinfunction "GPIO5/RTC_GPIO5/__TOUCH5/_ADC1_CH4_9") (pintype "passive"))
    )
    (net (code "29") (name "/GPIO6") (class "Default")
      (node (ref "J2") (pin "16") (pinfunction "16_16") (pintype "passive"))
      (node (ref "U3") (pin "10") (pinfunction "GPIO6/RTC_GPIO6/__TOUCH6/_ADC1_CH5_10") (pintype "passive"))
    )
    (net (code "30") (name "/GPIO7") (class "Default")
      (node (ref "J2") (pin "15") (pinfunction "15_15") (pintype "passive"))
      (node (ref "U3") (pin "11") (pinfunction "GPIO7/RTC_GPIO7/_TOUCH7/_ADC1_CH6_11") (pintype "passive"))
    )
    (net (code "31") (name "/GPIO8") (class "Default")
      (node (ref "J2") (pin "14") (pinfunction "14_14") (pintype "passive"))
      (node (ref "U3") (pin "12") (pinfunction "GPIO8/RTC_GPIO8/_TOUCH8/_ADC1_CH7/_SUBSPICS1_12") (pintype "passive"))
    )
    (net (code "32") (name "/GPIO9") (class "Default")
      (node (ref "J2") (pin "13") (pinfunction "13_13") (pintype "passive"))
      (node (ref "U3") (pin "13") (pinfunction "GPIO9/_RTC_GPIO9/TOUCH9/_ADC1_CH8/_FSPIHD/_SUBSPIHD_13") (pintype "passive"))
    )
    (net (code "33") (name "/GPIO10") (class "Default")
      (node (ref "J2") (pin "12") (pinfunction "12_12") (pintype "passive"))
      (node (ref "U3") (pin "14") (pinfunction "GPIO10/RTC_GPIO10/__TOUCH10/_ADC1_CH9/_FSPICS0/_FSPIIO4/_14") (pintype "passive"))
    )
    (net (code "34") (name "/GPIO11") (class "Default")
      (node (ref "J2") (pin "11") (pinfunction "11_11") (pintype "passive"))
      (node (ref "U3") (pin "15") (pinfunction "GPIO11/RTC_GPIO11/_TOUCH11/_ADC2_CH0/_FSPID/_FSPIIO5/_SUBSPID_15") (pintype "passive"))
    )
    (net (code "35") (name "/GPIO12") (class "Default")
      (node (ref "J2") (pin "10") (pinfunction "10_10") (pintype "passive"))
      (node (ref "U3") (pin "16") (pinfunction "GPIO12/RTC_GPIO12/__TOUCH12/_ADC2_CH1/_FSPICLK/_FSPIIO6/_16") (pintype "passive"))
    )
    (net (code "36") (name "/GPIO13") (class "Default")
      (node (ref "J2") (pin "9") (pinfunction "9_9") (pintype "passive"))
      (node (ref "U3") (pin "17") (pinfunction "GPIO13/RTC_GPIO13/_TOUCH13/_ADC2_CH2/_FSPIQ/_FSPIIO7/_SUBSPIQ_17") (pintype "passive"))
    )
    (net (code "37") (name "/GPIO14") (class "Default")
      (node (ref "J2") (pin "8") (pinfunction "8_8") (pintype "passive"))
      (node (ref "U3") (pin "18") (pinfunction "GPIO14/_RTC_GPIO14/_TOUCH14/_ADC2_CH3/_FSPIWP/_FSPIDQS/_18") (pintype "passive"))
    )
    (net (code "38") (name "/GPIO15") (class "Default")
      (node (ref "J2") (pin "7") (pinfunction "7_7") (pintype "passive"))
      (node (ref "U3") (pin "19") (pinfunction "GPIO15/_RTC_GPIO15/_U0RTS/_ADC2_CH4/_XTAL_32K_P_19") (pintype "passive"))
    )
    (net (code "39") (name "/GPIO16") (class "Default")
      (node (ref "J2") (pin "6") (pinfunction "6_6") (pintype "passive"))
      (node (ref "U3") (pin "20") (pinfunction "GPIO16/RTC_GPIO16/_U0CTS/_ADC2_CH5/_XTAL_32K_N_20") (pintype "passive"))
    )
    (net (code "40") (name "/GPIO17") (class "Default")
      (node (ref "J2") (pin "5") (pinfunction "5_5") (pintype "passive"))
      (node (ref "U3") (pin "21") (pinfunction "GPIO17/_RTC_GPIO17/_U1TXD/_ADC2_CH6_21") (pintype "passive"))
    )
    (net (code "41") (name "/GPIO18") (class "Default")
      (node (ref "J2") (pin "4") (pinfunction "4_4") (pintype "passive"))
      (node (ref "U3") (pin "22") (pinfunction "GPIO18/RTC_GPIO18/__U1RXD/_ADC2_CH7/_CLK_OUT3_22") (pintype "passive"))
    )
    (net (code "42") (name "/GPIO21") (class "Default")
      (node (ref "J3") (pin "6") (pinfunction "6_6") (pintype "passive"))
      (node (ref "U3") (pin "25") (pinfunction "GPIO21/RTC_GPIO21_25") (pintype "passive"))
    )
    (net (code "43") (name "/GPIO26") (class "Default")
      (node (ref "J3") (pin "7") (pinfunction "7_7") (pintype "passive"))
      (node (ref "U3") (pin "26") (pinfunction "GPIO26/SPICS1_26") (pintype "passive"))
    )
    (net (code "44") (name "/GPIO33") (class "Default")
      (node (ref "J3") (pin "8") (pinfunction "8_8") (pintype "passive"))
      (node (ref "U3") (pin "28") (pinfunction "GPIO33/_SPIIO4/_FSPIHD/_SUBSPIHD_28") (pintype "passive"))
    )
    (net (code "45") (name "/GPIO34") (class "Default")
      (node (ref "J3") (pin "9") (pinfunction "9_9") (pintype "passive"))
      (node (ref "U3") (pin "29") (pinfunction "GPIO34/_SPIIO5/_FSPICS0/_SUBSPICS0_29") (pintype "passive"))
    )
    (net (code "46") (name "/GPIO35") (class "Default")
      (node (ref "J3") (pin "10") (pinfunction "10_10") (pintype "passive"))
      (node (ref "U3") (pin "31") (pinfunction "GPIO35_/_SPIIO6/__FSPID/_SUBSPID_31") (pintype "passive"))
    )
    (net (code "47") (name "/GPIO36") (class "Default")
      (node (ref "J3") (pin "11") (pinfunction "11_11") (pintype "passive"))
      (node (ref "U3") (pin "32") (pinfunction "GPIO36/SPIIO7/__FSPICLK/_SUBSPICLK_32") (pintype "passive"))
    )
    (net (code "48") (name "/GPIO37") (class "Default")
      (node (ref "J3") (pin "12") (pinfunction "12_12") (pintype "passive"))
      (node (ref "U3") (pin "33") (pinfunction "GPIO37/_SPIDQS/_FSPIQ/_SUBSPIQ_33") (pintype "passive"))
    )
    (net (code "49") (name "/GPIO38") (class "Default")
      (node (ref "J3") (pin "13") (pinfunction "13_13") (pintype "passive"))
      (node (ref "U3") (pin "34") (pinfunction "GPIO38/_FSPIWP/_SUBSPIWP_34") (pintype "passive"))
    )
    (net (code "50") (name "/GPIO39") (class "Default")
      (node (ref "J3") (pin "14") (pinfunction "14_14") (pintype "passive"))
      (node (ref "U3") (pin "35") (pinfunction "MTCK/_GPIO39/CLK_OUT3/_SUBSPICS1_35") (pintype "passive"))
    )
    (net (code "51") (name "/GPIO40") (class "Default")
      (node (ref "J3") (pin "15") (pinfunction "15_15") (pintype "passive"))
      (node (ref "U3") (pin "36") (pinfunction "MTDO/_GPIO40/_CLK_OUT2_36") (pintype "passive"))
    )
    (net (code "52") (name "/GPIO41") (class "Default")
      (node (ref "J3") (pin "16") (pinfunction "16_16") (pintype "passive"))
      (node (ref "U3") (pin "37") (pinfunction "MTDI/_GPIO41/_CLK_OUT1_37") (pintype "passive"))
    )
    (net (code "53") (name "/GPIO42") (class "Default")
      (node (ref "J3") (pin "17") (pinfunction "17_17") (pintype "passive"))
      (node (ref "U3") (pin "38") (pinfunction "MTMS/_GPIO42_38") (pintype "passive"))
    )
    (net (code "54") (name "/GPIO45") (class "Default")
      (node (ref "J3") (pin "20") (pinfunction "20_20") (pintype "passive"))
      (node (ref "U3") (pin "41") (pinfunction "GPIO45_41") (pintype "passive"))
    )
    (net (code "55") (name "/GPIO46") (class "Default")
      (node (ref "J3") (pin "21") (pinfunction "21_21") (pintype "passive"))
      (node (ref "U3") (pin "44") (pinfunction "GPIO46_44") (pintype "passive"))
    )
    (net (code "56") (name "/GPIO47") (class "Default")
      (node (ref "J3") (pin "2") (pinfunction "2_2") (pintype "passive"))
      (node (ref "U3") (pin "27") (pinfunction "GPIO47/SPICLK_P_DIFF/_SUBSPICLK_P_DIFF_27") (pintype "passive"))
    )
    (net (code "57") (name "/GPIO48") (class "Default")
      (node (ref "J3") (pin "3") (pinfunction "3_3") (pintype "passive"))
      (node (ref "U3") (pin "30") (pinfunction "GPIO48_/_SPICLK_N_DIFF/__SUBSPICLK_N_DIFF_30") (pintype "passive"))
    )
    (net (code "58") (name "/RTS_FTDI") (class "Default")
      (node (ref "Q1") (pin "2") (pinfunction "E_2") (pintype "passive"))
      (node (ref "R14") (pin "1") (pinfunction "1_1") (pintype "passive"))
      (node (ref "U2") (pin "19") (pinfunction "~{RTS}_19") (pintype "output"))
    )
    (net (code "59") (name "/RXD_FTDI") (class "Default")
      (node (ref "R19") (pin "2") (pinfunction "2_2") (pintype "passive"))
      (node (ref "U2") (pin "1") (pinfunction "RXD_1") (pintype "output"))
    )
    (net (code "60") (name "/TXD_FTDI") (class "Default")
      (node (ref "R20") (pin "2") (pinfunction "2_2") (pintype "passive"))
      (node (ref "U2") (pin "17") (pinfunction "TXD_17") (pintype "output"))
    )
    (net (code "61") (name "/U0RXD") (class "Default")
      (node (ref "J3") (pin "19") (pinfunction "19_19") (pintype "passive"))
      (node (ref "R20") (pin "1") (pinfunction "1_1") (pintype "passive"))
      (node (ref "U3") (pin "40") (pinfunction "U0RXD/_GPIO44/_CLK_OUT2_40") (pintype "passive"))
    )
    (net (code "62") (name "/U0TXD") (class "Default")
      (node (ref "J3") (pin "18") (pinfunction "18_18") (pintype "passive"))
      (node (ref "R19") (pin "1") (pinfunction "1_1") (pintype "passive"))
      (node (ref "U3") (pin "39") (pinfunction "U0TXD/_GPIO43/_CLK_OUT1_39") (pintype "passive"))
    )
    (net (code "63") (name "/VBUS_SENSE") (class "Default")
      (node (ref "R10") (pin "1") (pinfunction "1_1") (pintype "passive"))
      (node (ref "R15") (pin "1") (pinfunction "1_1") (pintype "passive"))
      (node (ref "U2") (pin "16") (pinfunction "CBUS3_16") (pintype "bidirectional"))
    )
    (net (code "64") (name "GND") (class "Default")
      (node (ref "C1") (pin "1") (pinfunction "1_1") (pintype "passive"))
      (node (ref "C10") (pin "1") (pinfunction "1_1") (pintype "passive"))
      (node (ref "C11") (pin "1") (pinfunction "1_1") (pintype "passive"))
      (node (ref "C12") (pin "1") (pinfunction "1_1") (pintype "passive"))
      (node (ref "C13") (pin "1") (pinfunction "1_1") (pintype "passive"))
      (node (ref "C14") (pin "1") (pinfunction "1_1") (pintype "passive"))
      (node (ref "C15") (pin "1") (pinfunction "1_1") (pintype "passive"))
      (node (ref "C16") (pin "1") (pinfunction "1_1") (pintype "passive"))
      (node (ref "C17") (pin "1") (pinfunction "1_1") (pintype "passive"))
      (node (ref "C2") (pin "1") (pinfunction "1_1") (pintype "passive"))
      (node (ref "C3") (pin "1") (pinfunction "1_1") (pintype "passive"))
      (node (ref "C4") (pin "1") (pinfunction "1_1") (pintype "passive"))
      (node (ref "C5") (pin "1") (pinfunction "1_1") (pintype "passive"))
      (node (ref "C6") (pin "1") (pinfunction "1_1") (pintype "passive"))
      (node (ref "C7") (pin "1") (pinfunction "1_1") (pintype "passive"))
      (node (ref "C8") (pin "1") (pinfunction "1_1") (pintype "passive"))
      (node (ref "C9") (pin "1") (pinfunction "1_1") (pintype "passive"))
      (node (ref "D1") (pin "1") (pinfunction "1_1") (pintype "passive"))
      (node (ref "D3") (pin "1") (pinfunction "1_1") (pintype "passive"))
      (node (ref "D4") (pin "1") (pinfunction "1_1") (pintype "passive"))
      (node (ref "D5") (pin "1") (pinfunction "1_1") (pintype "passive"))
      (node (ref "D6") (pin "1") (pinfunction "1_1") (pintype "passive"))
      (node (ref "D7") (pin "1") (pinfunction "1_1") (pintype "passive"))
      (node (ref "D8") (pin "1") (pinfunction "1_1") (pintype "passive"))
      (node (ref "J1") (pin "A1B12") (pinfunction "GND_A1B12_A1B12") (pintype "passive"))
      (node (ref "J1") (pin "B1A12") (pinfunction "GND_B1A12_B1A12") (pintype "passive"))
      (node (ref "J1") (pin "S1") (pinfunction "SHIELD_1_S1") (pintype "passive"))
      (node (ref "J1") (pin "S2") (pinfunction "SHIELD_2_S2") (pintype "passive"))
      (node (ref "J1") (pin "S3") (pinfunction "SHIELD_3_S3") (pintype "passive"))
      (node (ref "J1") (pin "S4") (pinfunction "SHIELD_4_S4") (pintype "passive"))
      (node (ref "J2") (pin "2") (pinfunction "2_2") (pintype "passive"))
      (node (ref "J2") (pin "24") (pinfunction "24_24") (pintype "passive"))
      (node (ref "J3") (pin "1") (pinfunction "1_1") (pintype "passive"))
      (node (ref "J3") (pin "23") (pinfunction "23_23") (pintype "passive"))
      (node (ref "J6") (pin "A1B12") (pinfunction "GND_A1B12_A1B12") (pintype "passive"))
      (node (ref "J6") (pin "B1A12") (pinfunction "GND_B1A12_B1A12") (pintype "passive"))
      (node (ref "J6") (pin "S1") (pinfunction "SHIELD_1_S1") (pintype "passive"))
      (node (ref "J6") (pin "S2") (pinfunction "SHIELD_2_S2") (pintype "passive"))
      (node (ref "J6") (pin "S3") (pinfunction "SHIELD_3_S3") (pintype "passive"))
      (node (ref "J6") (pin "S4") (pinfunction "SHIELD_4_S4") (pintype "passive"))
      (node (ref "R13") (pin "2") (pinfunction "2_2") (pintype "passive"))
      (node (ref "R15") (pin "2") (pinfunction "2_2") (pintype "passive"))
      (node (ref "R16") (pin "1") (pinfunction "1_1") (pintype "passive"))
      (node (ref "R17") (pin "1") (pinfunction "1_1") (pintype "passive"))
      (node (ref "R3") (pin "1") (pinfunction "1_1") (pintype "passive"))
      (node (ref "R4") (pin "1") (pinfunction "1_1") (pintype "passive"))
      (node (ref "SW1") (pin "3") (pinfunction "3_3") (pintype "passive"))
      (node (ref "SW1") (pin "4") (pinfunction "4_4") (pintype "passive"))
      (node (ref "SW2") (pin "3") (pinfunction "3_3") (pintype "passive"))
      (node (ref "SW2") (pin "4") (pinfunction "4_4") (pintype "passive"))
      (node (ref "U1") (pin "2") (pinfunction "GND_2") (pintype "power_in"))
      (node (ref "U1") (pin "4") (pinfunction "GND_4") (pintype "power_in"))
      (node (ref "U2") (pin "13") (pinfunction "GND_13") (pintype "passive"))
      (node (ref "U2") (pin "21") (pinfunction "GND_21") (pintype "power_in"))
      (node (ref "U2") (pin "3") (pinfunction "GND_3") (pintype "power_in"))
      (node (ref "U3") (pin "1") (pinfunction "GND_1_1") (pintype "passive"))
      (node (ref "U3") (pin "2") (pinfunction "GND_2_2") (pintype "passive"))
      (node (ref "U3") (pin "42") (pinfunction "GND_42_42") (pintype "passive"))
      (node (ref "U3") (pin "43") (pinfunction "GND_43_43") (pintype "passive"))
      (node (ref "U3") (pin "46") (pinfunction "GND_46_46") (pintype "passive"))
      (node (ref "U3") (pin "47") (pinfunction "GND_47_47") (pintype "passive"))
      (node (ref "U3") (pin "48") (pinfunction "GND_48_48") (pintype "passive"))
      (node (ref "U3") (pin "49") (pinfunction "GND_49_49") (pintype "passive"))
      (node (ref "U3") (pin "50") (pinfunction "GND_50_50") (pintype "passive"))
      (node (ref "U3") (pin "51") (pinfunction "GND_51_51") (pintype "passive"))
      (node (ref "U3") (pin "52") (pinfunction "GND_52_52") (pintype "passive"))
      (node (ref "U3") (pin "53") (pinfunction "GND_53_53") (pintype "passive"))
      (node (ref "U3") (pin "54") (pinfunction "GND_54_54") (pintype "passive"))
      (node (ref "U3") (pin "55") (pinfunction "GND_55_55") (pintype "passive"))
      (node (ref "U3") (pin "56") (pinfunction "GND_56_56") (pintype "passive"))
      (node (ref "U3") (pin "57") (pinfunction "GND_57_57") (pintype "passive"))
      (node (ref "U3") (pin "58") (pinfunction "GND_58_58") (pintype "passive"))
      (node (ref "U3") (pin "59") (pinfunction "GND_59_59") (pintype "passive"))
      (node (ref "U3") (pin "60") (pinfunction "GND_60_60") (pintype "passive"))
      (node (ref "U3") (pin "61") (pinfunction "GND_61_61") (pintype "passive"))
      (node (ref "U3") (pin "62") (pinfunction "GND_62_62") (pintype "passive"))
      (node (ref "U3") (pin "63") (pinfunction "GND_63_63") (pintype "passive"))
      (node (ref "U3") (pin "64") (pinfunction "GND_64_64") (pintype "passive"))
      (node (ref "U3") (pin "65") (pinfunction "GND_65_65") (pintype "passive"))
      (node (ref "U3") (pin "66") (pinfunction "GND_66_66") (pintype "passive"))
      (node (ref "U3") (pin "67") (pinfunction "GND_67_67") (pintype "passive"))
      (node (ref "U3") (pin "68") (pinfunction "GND_68_68") (pintype "passive"))
      (node (ref "U3") (pin "69") (pinfunction "GND_69_69") (pintype "passive"))
      (node (ref "U3") (pin "70") (pinfunction "GND_70_70") (pintype "passive"))
      (node (ref "U3") (pin "71") (pinfunction "GND_71_71") (pintype "passive"))
      (node (ref "U3") (pin "72") (pinfunction "GND_72_72") (pintype "passive"))
      (node (ref "U3") (pin "73") (pinfunction "GND_73_73") (pintype "passive"))
    )
    (net (code "65") (name "Net-(D1-Pad2)") (class "Default")
      (node (ref "D1") (pin "2") (pinfunction "2_2") (pintype "passive"))
      (node (ref "R1") (pin "1") (pinfunction "1_1") (pintype "passive"))
    )
    (net (code "66") (name "Net-(D2-Pad2)") (class "Default")
      (node (ref "D2") (pin "2") (pinfunction "2_2") (pintype "passive"))
      (node (ref "R2") (pin "1") (pinfunction "1_1") (pintype "passive"))
    )
    (net (code "67") (name "Net-(J1-CC1)") (class "Default")
      (node (ref "J1") (pin "A5") (pinfunction "CC1_A5") (pintype "passive"))
      (node (ref "R4") (pin "2") (pinfunction "2_2") (pintype "passive"))
    )
    (net (code "68") (name "Net-(J1-CC2)") (class "Default")
      (node (ref "J1") (pin "B5") (pinfunction "CC2_B5") (pintype "passive"))
      (node (ref "R3") (pin "2") (pinfunction "2_2") (pintype "passive"))
    )
    (net (code "69") (name "Net-(J6-CC1)") (class "Default")
      (node (ref "J6") (pin "A5") (pinfunction "CC1_A5") (pintype "passive"))
      (node (ref "R17") (pin "2") (pinfunction "2_2") (pintype "passive"))
    )
    (net (code "70") (name "Net-(J6-CC2)") (class "Default")
      (node (ref "J6") (pin "B5") (pinfunction "CC2_B5") (pintype "passive"))
      (node (ref "R16") (pin "2") (pinfunction "2_2") (pintype "passive"))
    )
    (net (code "71") (name "Net-(Q1-B)") (class "Default")
      (node (ref "Q1") (pin "1") (pinfunction "B_1") (pintype "passive"))
      (node (ref "R7") (pin "2") (pinfunction "2_2") (pintype "passive"))
    )
    (net (code "72") (name "Net-(Q2-B)") (class "Default")
      (node (ref "Q2") (pin "1") (pinfunction "B_1") (pintype "passive"))
      (node (ref "R14") (pin "2") (pinfunction "2_2") (pintype "passive"))
    )
    (net (code "73") (name "Net-(U2-CBUS0)") (class "Default")
      (node (ref "R13") (pin "1") (pinfunction "1_1") (pintype "passive"))
      (node (ref "U2") (pin "15") (pinfunction "CBUS0_15") (pintype "bidirectional"))
    )
    (net (code "74") (name "unconnected-(J1-SBU1-PadA8)") (class "Default")
      (node (ref "J1") (pin "A8") (pinfunction "SBU1_A8") (pintype "passive+no_connect"))
    )
    (net (code "75") (name "unconnected-(J1-SBU2-PadB8)") (class "Default")
      (node (ref "J1") (pin "B8") (pinfunction "SBU2_B8") (pintype "passive+no_connect"))
    )
    (net (code "76") (name "unconnected-(J2-Pad1)") (class "Default")
      (node (ref "J2") (pin "1") (pinfunction "1_1") (pintype "passive+no_connect"))
    )
    (net (code "77") (name "unconnected-(J6-SBU1-PadA8)") (class "Default")
      (node (ref "J6") (pin "A8") (pinfunction "SBU1_A8") (pintype "passive+no_connect"))
    )
    (net (code "78") (name "unconnected-(J6-SBU2-PadB8)") (class "Default")
      (node (ref "J6") (pin "B8") (pinfunction "SBU2_B8") (pintype "passive+no_connect"))
    )
    (net (code "79") (name "unconnected-(U2-CBUS1-Pad14)") (class "Default")
      (node (ref "U2") (pin "14") (pinfunction "CBUS1_14") (pintype "bidirectional+no_connect"))
    )
    (net (code "80") (name "unconnected-(U2-CBUS2-Pad7)") (class "Default")
      (node (ref "U2") (pin "7") (pinfunction "CBUS2_7") (pintype "bidirectional+no_connect"))
    )
    (net (code "81") (name "unconnected-(U2-~{CTS}-Pad6)") (class "Default")
      (node (ref "U2") (pin "6") (pinfunction "~{CTS}_6") (pintype "input+no_connect"))
    )
    (net (code "82") (name "unconnected-(U2-~{DCD}-Pad5)") (class "Default")
      (node (ref "U2") (pin "5") (pinfunction "~{DCD}_5") (pintype "input+no_connect"))
    )
    (net (code "83") (name "unconnected-(U2-~{DSR}-Pad4)") (class "Default")
      (node (ref "U2") (pin "4") (pinfunction "~{DSR}_4") (pintype "input+no_connect"))
    )
    (net (code "84") (name "unconnected-(U2-~{RI}-Pad2)") (class "Default")
      (node (ref "U2") (pin "2") (pinfunction "~{RI}_2") (pintype "input+no_connect"))
    )
  )
)
